# AdvancedCircuit.net
KiCad netlist of a schematic drawn in EAGLE
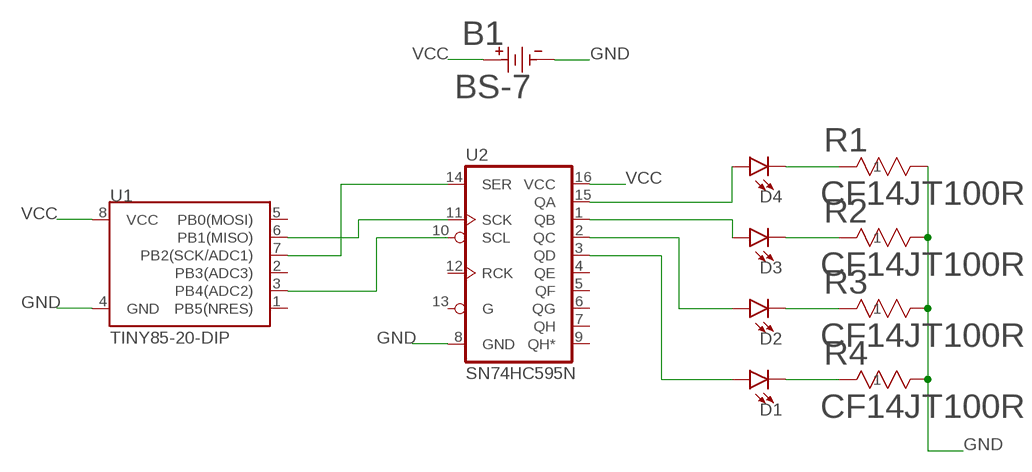
[diagram p0: schematic, sheet 1]

(export (version "E")
  (design (tool "Eeschema 10.0.6"))
  (components
    (comp (ref "B1")
      (value "BS-7")
      (footprint "eagle-import:BS-7_MPD")
      (fields (field (name "COPYRIGHT") "Copyright (C) 2018 Accelerated Designs. All rights reserved"))
      (libsource (lib "eagle-import") (part "BS-7"))
    )
    (comp (ref "D1")
      (value "LED3MM")
      (footprint "eagle-import:LED_3MM")
      (libsource (lib "eagle-import") (part "LED3MM"))
    )
    (comp (ref "D2")
      (value "LED3MM")
      (footprint "eagle-import:LED_3MM")
      (libsource (lib "eagle-import") (part "LED3MM"))
    )
    (comp (ref "D3")
      (value "LED3MM")
      (footprint "eagle-import:LED_3MM")
      (libsource (lib "eagle-import") (part "LED3MM"))
    )
    (comp (ref "D4")
      (value "LED3MM")
      (footprint "eagle-import:LED_3MM")
      (libsource (lib "eagle-import") (part "LED3MM"))
    )
    (comp (ref "R1")
      (value "CF14JT100R")
      (footprint "eagle-import:STA_CF14_STP")
      (libsource (lib "eagle-import") (part "CF14JT100R"))
    )
    (comp (ref "R2")
      (value "CF14JT100R")
      (footprint "eagle-import:STA_CF14_STP")
      (libsource (lib "eagle-import") (part "CF14JT100R"))
    )
    (comp (ref "R3")
      (value "CF14JT100R")
      (footprint "eagle-import:STA_CF14_STP")
      (libsource (lib "eagle-import") (part "CF14JT100R"))
    )
    (comp (ref "R4")
      (value "CF14JT100R")
      (footprint "eagle-import:STA_CF14_STP")
      (libsource (lib "eagle-import") (part "CF14JT100R"))
    )
    (comp (ref "U1")
      (value "TINY85-20-DIP")
      (footprint "eagle-import:DIP08_MCU")
      (libsource (lib "eagle-import") (part "ATTINY45TINY85-20-DIP"))
    )
    (comp (ref "U2")
      (value "SN74HC595N")
      (footprint "eagle-import:DIP16")
      (libsource (lib "eagle-import") (part "74595NHC"))
    )
  )
  (nets
    (net (code "1") (name "/GND") (class "Default")
      (node (ref "B1") (pin "1") (pinfunction "1_1") (pintype "passive"))
      (node (ref "R1") (pin "2") (pinfunction "2_2") (pintype "passive"))
      (node (ref "R2") (pin "2") (pinfunction "2_2") (pintype "passive"))
      (node (ref "R3") (pin "2") (pinfunction "2_2") (pintype "passive"))
      (node (ref "R4") (pin "2") (pinfunction "2_2") (pintype "passive"))
      (node (ref "U1") (pin "4") (pinfunction "GND_4") (pintype "bidirectional"))
      (node (ref "U2") (pin "8") (pinfunction "GND_8") (pintype "power_in"))
    )
    (net (code "2") (name "/VCC") (class "Default")
      (node (ref "B1") (pin "2") (pinfunction "2_2") (pintype "passive"))
      (node (ref "U1") (pin "8") (pinfunction "VCC_8") (pintype "bidirectional"))
      (node (ref "U2") (pin "16") (pinfunction "VCC_16") (pintype "power_in"))
    )
    (net (code "3") (name "Net-(D1-C)") (class "Default")
      (node (ref "D1") (pin "K") (pinfunction "C_K") (pintype "passive"))
      (node (ref "R4") (pin "1") (pinfunction "1_1") (pintype "passive"))
    )
    (net (code "4") (name "Net-(D2-C)") (class "Default")
      (node (ref "D2") (pin "K") (pinfunction "C_K") (pintype "passive"))
      (node (ref "R3") (pin "1") (pinfunction "1_1") (pintype "passive"))
    )
    (net (code "5") (name "Net-(D3-C)") (class "Default")
      (node (ref "D3") (pin "K") (pinfunction "C_K") (pintype "passive"))
      (node (ref "R2") (pin "1") (pinfunction "1_1") (pintype "passive"))
    )
    (net (code "6") (name "Net-(D4-C)") (class "Default")
      (node (ref "D4") (pin "K") (pinfunction "C_K") (pintype "passive"))
      (node (ref "R1") (pin "1") (pinfunction "1_1") (pintype "passive"))
    )
    (net (code "7") (name "Net-(U1-PB1(MISO))") (class "Default")
      (node (ref "U1") (pin "6") (pinfunction "PB1(MISO)_6") (pintype "bidirectional"))
      (node (ref "U2") (pin "11") (pinfunction "SCK_11") (pintype "input"))
    )
    (net (code "8") (name "Net-(U1-PB2(SCK{slash}ADC1))") (class "Default")
      (node (ref "U1") (pin "7") (pinfunction "PB2(SCK/ADC1)_7") (pintype "bidirectional"))
      (node (ref "U2") (pin "14") (pinfunction "SER_14") (pintype "input"))
    )
    (net (code "9") (name "Net-(U1-PB4(ADC2))") (class "Default")
      (node (ref "U1") (pin "3") (pinfunction "PB4(ADC2)_3") (pintype "bidirectional"))
      (node (ref "U2") (pin "10") (pinfunction "SCL_10") (pintype "input"))
    )
    (net (code "10") (name "Net-(U2-QA)") (class "Default")
      (node (ref "D4") (pin "A") (pinfunction "A_A") (pintype "passive"))
      (node (ref "U2") (pin "15") (pinfunction "QA_15") (pintype "tri_state"))
    )
    (net (code "11") (name "Net-(U2-QB)") (class "Default")
      (node (ref "D3") (pin "A") (pinfunction "A_A") (pintype "passive"))
      (node (ref "U2") (pin "1") (pinfunction "QB_1") (pintype "tri_state"))
    )
    (net (code "12") (name "Net-(U2-QC)") (class "Default")
      (node (ref "D2") (pin "A") (pinfunction "A_A") (pintype "passive"))
      (node (ref "U2") (pin "2") (pinfunction "QC_2") (pintype "tri_state"))
    )
    (net (code "13") (name "Net-(U2-QD)") (class "Default")
      (node (ref "D1") (pin "A") (pinfunction "A_A") (pintype "passive"))
      (node (ref "U2") (pin "3") (pinfunction "QD_3") (pintype "tri_state"))
    )
    (net (code "14") (name "unconnected-(U1-PB0(MOSI)-Pad5)") (class "Default")
      (node (ref "U1") (pin "5") (pinfunction "PB0(MOSI)_5") (pintype "bidirectional"))
    )
    (net (code "15") (name "unconnected-(U1-PB3(ADC3)-Pad2)") (class "Default")
      (node (ref "U1") (pin "2") (pinfunction "PB3(ADC3)_2") (pintype "bidirectional"))
    )
    (net (code "16") (name "unconnected-(U1-PB5(NRES)-Pad1)") (class "Default")
      (node (ref "U1") (pin "1") (pinfunction "PB5(NRES)_1") (pintype "bidirectional"))
    )
    (net (code "17") (name "unconnected-(U2-G-Pad13)") (class "Default")
      (node (ref "U2") (pin "13") (pinfunction "G_13") (pintype "input"))
    )
    (net (code "18") (name "unconnected-(U2-QE-Pad4)") (class "Default")
      (node (ref "U2") (pin "4") (pinfunction "QE_4") (pintype "tri_state"))
    )
    (net (code "19") (name "unconnected-(U2-QF-Pad5)") (class "Default")
      (node (ref "U2") (pin "5") (pinfunction "QF_5") (pintype "tri_state"))
    )
    (net (code "20") (name "unconnected-(U2-QG-Pad6)") (class "Default")
      (node (ref "U2") (pin "6") (pinfunction "QG_6") (pintype "tri_state"))
    )
    (net (code "21") (name "unconnected-(U2-QH*-Pad9)") (class "Default")
      (node (ref "U2") (pin "9") (pinfunction "QH*_9") (pintype "tri_state"))
    )
    (net (code "22") (name "unconnected-(U2-QH-Pad7)") (class "Default")
      (node (ref "U2") (pin "7") (pinfunction "QH_7") (pintype "tri_state"))
    )
    (net (code "23") (name "unconnected-(U2-RCK-Pad12)") (class "Default")
      (node (ref "U2") (pin "12") (pinfunction "RCK_12") (pintype "input"))
    )
  )
)
